# street_light.net
KiCad netlist of a schematic drawn in EAGLE
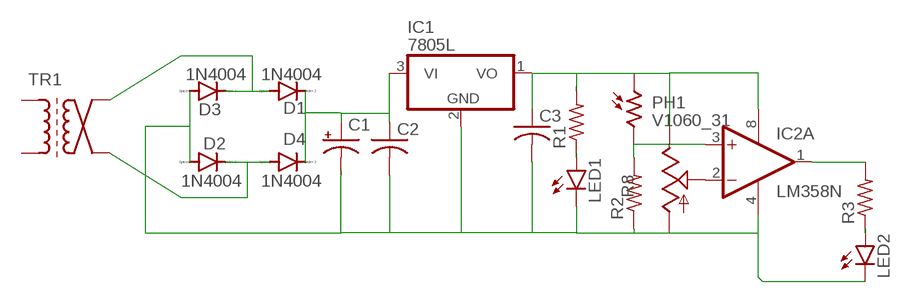
[diagram p0: schematic, sheet 1]

(export (version "E")
  (design (tool "Eeschema 10.0.6"))
  (components
    (comp (ref "C1")
      (value "CPOL-USE3.5-10")
      (footprint "eagle-import:E3,5-10")
      (libsource (lib "eagle-import") (part "CPOL-USE3.5-10"))
    )
    (comp (ref "C2")
      (value "C-US025-024X044")
      (footprint "eagle-import:C025-024X044")
      (libsource (lib "eagle-import") (part "C-US025-024X044"))
    )
    (comp (ref "C3")
      (value "C-US025-024X044")
      (footprint "eagle-import:C025-024X044")
      (libsource (lib "eagle-import") (part "C-US025-024X044"))
    )
    (comp (ref "D1")
      (value "1N4004")
      (footprint "eagle-import:DO41-10")
      (libsource (lib "eagle-import") (part "1N4004"))
    )
    (comp (ref "D2")
      (value "1N4004")
      (footprint "eagle-import:DO41-10")
      (libsource (lib "eagle-import") (part "1N4004"))
    )
    (comp (ref "D3")
      (value "1N4004")
      (footprint "eagle-import:DO41-10")
      (libsource (lib "eagle-import") (part "1N4004"))
    )
    (comp (ref "D4")
      (value "1N4004")
      (footprint "eagle-import:DO41-10")
      (libsource (lib "eagle-import") (part "1N4004"))
    )
    (comp (ref "IC1")
      (value "7805L")
      (footprint "eagle-import:TO92")
      (libsource (lib "eagle-import") (part "78L05"))
    )
    (comp (ref "IC2")
      (value "LM358N")
      (footprint "eagle-import:DIL08")
      (libsource (lib "eagle-import") (part "LM358N"))
    )
    (comp (ref "LED1")
      (value "LED5MM")
      (footprint "eagle-import:LED5MM")
      (libsource (lib "eagle-import") (part "LED5MM"))
    )
    (comp (ref "LED2")
      (value "LED5MM")
      (footprint "eagle-import:LED5MM")
      (libsource (lib "eagle-import") (part "LED5MM"))
    )
    (comp (ref "PH1")
      (value "V1060_31")
      (footprint "eagle-import:TO-5_V10")
      (libsource (lib "eagle-import") (part "?1060V_31"))
    )
    (comp (ref "R1")
      (value "R-US_0207/10")
      (footprint "eagle-import:0207_10")
      (libsource (lib "eagle-import") (part "R-US_0207/10"))
    )
    (comp (ref "R2")
      (value "R-US_0207/10")
      (footprint "eagle-import:0207_10")
      (libsource (lib "eagle-import") (part "R-US_0207/10"))
    )
    (comp (ref "R3")
      (value "R-US_0207/10")
      (footprint "eagle-import:0207_10")
      (libsource (lib "eagle-import") (part "R-US_0207/10"))
    )
    (comp (ref "R8")
      (value "TRIM_US-CA6V")
      (footprint "eagle-import:CA6V")
      (libsource (lib "eagle-import") (part "TRIM_US-CA6V"))
    )
    (comp (ref "TR1")
      (value "MS35B")
      (footprint "eagle-import:MS35B")
      (libsource (lib "eagle-import") (part "MS35B"))
    )
  )
  (nets
    (net (code "1") (name "Net-(D1-PadA)") (class "Default")
      (node (ref "D1") (pin "A") (pinfunction "A_A") (pintype "passive"))
      (node (ref "D3") (pin "C") (pinfunction "C_C") (pintype "passive"))
      (node (ref "TR1") (pin "E2") (pinfunction "E2_E2") (pintype "passive"))
    )
    (net (code "2") (name "Net-(D2-PadC)") (class "Default")
      (node (ref "D2") (pin "C") (pinfunction "C_C") (pintype "passive"))
      (node (ref "D4") (pin "A") (pinfunction "A_A") (pintype "passive"))
      (node (ref "TR1") (pin "A2") (pinfunction "A2_A2") (pintype "passive"))
    )
    (net (code "3") (name "Net-(IC1-GND)") (class "Default")
      (node (ref "C1") (pin "-") (pinfunction "-_-") (pintype "passive"))
      (node (ref "C2") (pin "2") (pinfunction "2_2") (pintype "passive"))
      (node (ref "C3") (pin "2") (pinfunction "2_2") (pintype "passive"))
      (node (ref "D2") (pin "A") (pinfunction "A_A") (pintype "passive"))
      (node (ref "D3") (pin "A") (pinfunction "A_A") (pintype "passive"))
      (node (ref "IC1") (pin "2") (pinfunction "GND_2") (pintype "passive"))
      (node (ref "IC2") (pin "4") (pinfunction "V-_4") (pintype "power_in"))
      (node (ref "LED1") (pin "K") (pinfunction "C_K") (pintype "passive"))
      (node (ref "LED2") (pin "K") (pinfunction "C_K") (pintype "passive"))
      (node (ref "R2") (pin "1") (pinfunction "1_1") (pintype "passive"))
      (node (ref "R8") (pin "A") (pinfunction "A_A") (pintype "passive"))
    )
    (net (code "4") (name "Net-(IC1-VI)") (class "Default")
      (node (ref "C1") (pin "+") (pinfunction "+_+") (pintype "passive"))
      (node (ref "C2") (pin "1") (pinfunction "1_1") (pintype "passive"))
      (node (ref "D1") (pin "C") (pinfunction "C_C") (pintype "passive"))
      (node (ref "D4") (pin "C") (pinfunction "C_C") (pintype "passive"))
      (node (ref "IC1") (pin "3") (pinfunction "VI_3") (pintype "input"))
    )
    (net (code "5") (name "Net-(IC1-VO)") (class "Default")
      (node (ref "C3") (pin "1") (pinfunction "1_1") (pintype "passive"))
      (node (ref "IC1") (pin "1") (pinfunction "VO_1") (pintype "passive"))
      (node (ref "IC2") (pin "8") (pinfunction "V+_8") (pintype "power_in"))
      (node (ref "PH1") (pin "1") (pinfunction "1_1") (pintype "passive"))
      (node (ref "R1") (pin "2") (pinfunction "2_2") (pintype "passive"))
      (node (ref "R8") (pin "E") (pinfunction "E_E") (pintype "passive"))
    )
    (net (code "6") (name "Net-(IC2A-+IN)") (class "Default")
      (node (ref "IC2") (pin "3") (pinfunction "+IN_3") (pintype "input"))
      (node (ref "PH1") (pin "2") (pinfunction "2_2") (pintype "passive"))
      (node (ref "R2") (pin "2") (pinfunction "2_2") (pintype "passive"))
    )
    (net (code "7") (name "Net-(IC2A--IN)") (class "Default")
      (node (ref "IC2") (pin "2") (pinfunction "-IN_2") (pintype "input"))
      (node (ref "R8") (pin "S") (pinfunction "S_S") (pintype "passive"))
    )
    (net (code "8") (name "Net-(IC2A-OUT)") (class "Default")
      (node (ref "IC2") (pin "1") (pinfunction "OUT_1") (pintype "output"))
      (node (ref "R3") (pin "2") (pinfunction "2_2") (pintype "passive"))
    )
    (net (code "9") (name "Net-(LED1-PadA)") (class "Default")
      (node (ref "LED1") (pin "A") (pinfunction "A_A") (pintype "passive"))
      (node (ref "R1") (pin "1") (pinfunction "1_1") (pintype "passive"))
    )
    (net (code "10") (name "Net-(LED2-PadA)") (class "Default")
      (node (ref "LED2") (pin "A") (pinfunction "A_A") (pintype "passive"))
      (node (ref "R3") (pin "1") (pinfunction "1_1") (pintype "passive"))
    )
    (net (code "11") (name "unconnected-(TR1-PadA1)") (class "Default")
      (node (ref "TR1") (pin "A1") (pinfunction "A1_A1") (pintype "passive"))
    )
    (net (code "12") (name "unconnected-(TR1-PadE1)") (class "Default")
      (node (ref "TR1") (pin "E1") (pinfunction "E1_E1") (pintype "passive"))
    )
  )
)
